# Board_7_Segment.net
KiCad netlist of a schematic drawn in EAGLE
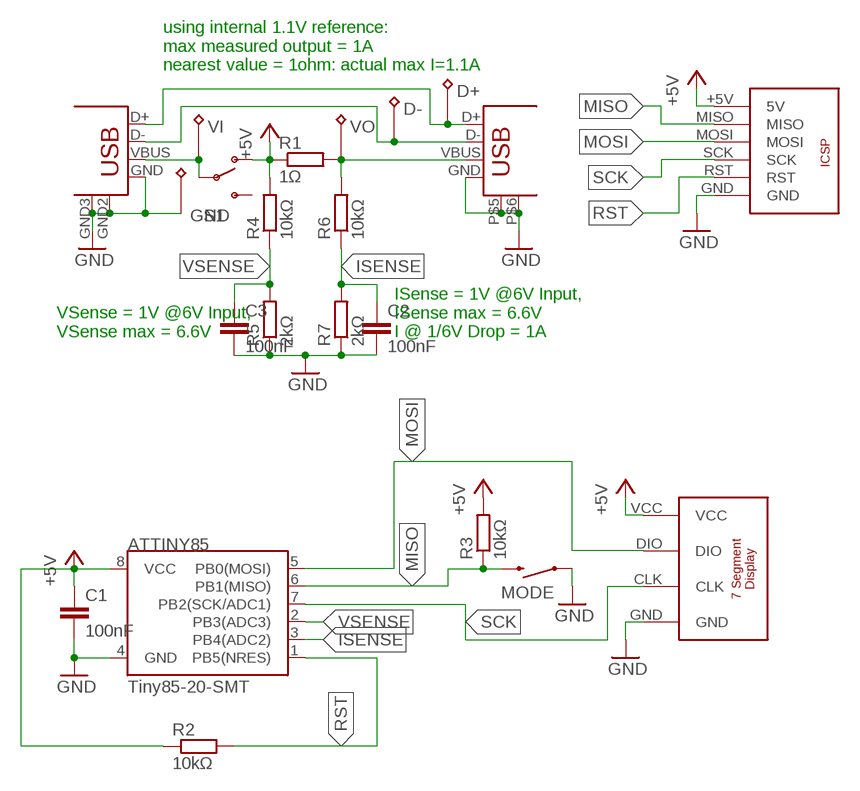
[diagram p0: schematic, sheet 1]

(export (version "E")
  (design (tool "Eeschema 10.0.6"))
  (components
    (comp (ref "ATTINY85")
      (value "Tiny85-20-SMT")
      (footprint "eagle-import:SO08-EIAJ")
      (libsource (lib "eagle-import") (part "ATTINY45TINY85-20-SMT"))
    )
    (comp (ref "C1")
      (value "100nF")
      (footprint "eagle-import:C0603")
      (libsource (lib "eagle-import") (part "C-EUC0603"))
    )
    (comp (ref "C2")
      (value "100nF")
      (footprint "eagle-import:C0603")
      (libsource (lib "eagle-import") (part "C-EUC0603"))
    )
    (comp (ref "C3")
      (value "100nF")
      (footprint "eagle-import:C0603")
      (libsource (lib "eagle-import") (part "C-EUC0603"))
    )
    (comp (ref "D+")
      (value "TESTPOINT0.8MM-DUAL-DRILL-WIRE-LOOP")
      (footprint "eagle-import:TP-0.8MM-DUAL")
      (libsource (lib "eagle-import") (part "TESTPOINT0.8MM-DUAL-DRILL-WIRE-LOOP"))
    )
    (comp (ref "D-")
      (value "TESTPOINT0.8MM-DUAL-DRILL-WIRE-LOOP")
      (footprint "eagle-import:TP-0.8MM-DUAL")
      (libsource (lib "eagle-import") (part "TESTPOINT0.8MM-DUAL-DRILL-WIRE-LOOP"))
    )
    (comp (ref "GND")
      (value "TESTPOINT0.8MM-DUAL-DRILL-WIRE-LOOP")
      (footprint "eagle-import:TP-0.8MM-DUAL")
      (libsource (lib "eagle-import") (part "TESTPOINT0.8MM-DUAL-DRILL-WIRE-LOOP"))
    )
    (comp (ref "INPUT")
      (value "USB+SHIELDTHROUGHHOLE-MALE")
      (footprint "eagle-import:USB-A-H")
      (libsource (lib "eagle-import") (part "USB+SHIELDTHROUGHHOLE-MALE"))
    )
    (comp (ref "MODE")
      (value "SWITCH-MOMENTARY-2SIDE_EZ")
      (footprint "eagle-import:TACTILE-PTH-SIDEEZ")
      (libsource (lib "eagle-import") (part "SWITCH-MOMENTARY-2SIDE_EZ"))
    )
    (comp (ref "OUTPUT")
      (value "USB+SHIELDTHROUGHOLE-FEMALE")
      (footprint "eagle-import:USB-A-S-SILK-THROUGHHOLE")
      (libsource (lib "eagle-import") (part "USB+SHIELDTHROUGHOLE-FEMALE"))
    )
    (comp (ref "R1")
      (value "1Ω")
      (footprint "eagle-import:R2512")
      (libsource (lib "eagle-import") (part "R-EU_R2512"))
    )
    (comp (ref "R2")
      (value "10kΩ")
      (footprint "eagle-import:R0603")
      (libsource (lib "eagle-import") (part "R-EU_R0603"))
    )
    (comp (ref "R3")
      (value "10kΩ")
      (footprint "eagle-import:R0603")
      (libsource (lib "eagle-import") (part "R-EU_R0603"))
    )
    (comp (ref "R4")
      (value "10kΩ")
      (footprint "eagle-import:R0603")
      (libsource (lib "eagle-import") (part "R-EU_R0603"))
    )
    (comp (ref "R5")
      (value "2kΩ")
      (footprint "eagle-import:R0603")
      (libsource (lib "eagle-import") (part "R-EU_R0603"))
    )
    (comp (ref "R6")
      (value "10kΩ")
      (footprint "eagle-import:R0603")
      (libsource (lib "eagle-import") (part "R-EU_R0603"))
    )
    (comp (ref "R7")
      (value "2kΩ")
      (footprint "eagle-import:R0603")
      (libsource (lib "eagle-import") (part "R-EU_R0603"))
    )
    (comp (ref "S1")
      (value "SWITCH-SPDT-SMD-A")
      (footprint "eagle-import:SWITCH-SPST-SMD-A")
      (libsource (lib "eagle-import") (part "SWITCH-SPDT-SMD-A"))
    )
    (comp (ref "U$1")
      (value "ICSPTHROUGHHOLE")
      (footprint "eagle-import:ICSP-THROUGHHOLE")
      (libsource (lib "eagle-import") (part "ICSPTHROUGHHOLE"))
    )
    (comp (ref "U$2")
      (value "7-SEGMENT-I2C")
      (footprint "eagle-import:7-SEGMENT-I2C")
      (libsource (lib "eagle-import") (part "7-SEGMENT-I2C"))
    )
    (comp (ref "VI")
      (value "TESTPOINT0.8MM-DUAL-DRILL-WIRE-LOOP")
      (footprint "eagle-import:TP-0.8MM-DUAL")
      (libsource (lib "eagle-import") (part "TESTPOINT0.8MM-DUAL-DRILL-WIRE-LOOP"))
    )
    (comp (ref "VO")
      (value "TESTPOINT0.8MM-DUAL-DRILL-WIRE-LOOP")
      (footprint "eagle-import:TP-0.8MM-DUAL")
      (libsource (lib "eagle-import") (part "TESTPOINT0.8MM-DUAL-DRILL-WIRE-LOOP"))
    )
  )
  (nets
    (net (code "1") (name "+5V") (class "Default")
      (node (ref "ATTINY85") (pin "8") (pinfunction "VCC_8") (pintype "bidirectional"))
      (node (ref "C1") (pin "1") (pinfunction "1_1") (pintype "passive"))
      (node (ref "R1") (pin "1") (pinfunction "1_1") (pintype "passive"))
      (node (ref "R2") (pin "1") (pinfunction "1_1") (pintype "passive"))
      (node (ref "R3") (pin "2") (pinfunction "2_2") (pintype "passive"))
      (node (ref "R4") (pin "2") (pinfunction "2_2") (pintype "passive"))
      (node (ref "S1") (pin "1") (pinfunction "O_1") (pintype "passive"))
      (node (ref "U$1") (pin "+5V") (pinfunction "5V_+5V") (pintype "bidirectional"))
      (node (ref "U$2") (pin "VCC") (pinfunction "VCC_VCC") (pintype "bidirectional"))
    )
    (net (code "2") (name "GND") (class "Default")
      (node (ref "ATTINY85") (pin "4") (pinfunction "GND_4") (pintype "bidirectional"))
      (node (ref "C1") (pin "2") (pinfunction "2_2") (pintype "passive"))
      (node (ref "C2") (pin "2") (pinfunction "2_2") (pintype "passive"))
      (node (ref "C3") (pin "2") (pinfunction "2_2") (pintype "passive"))
      (node (ref "GND") (pin "P$1") (pinfunction "TP_P$1") (pintype "bidirectional"))
      (node (ref "GND") (pin "P$2") (pinfunction "TP_P$2") (pintype "bidirectional"))
      (node (ref "INPUT") (pin "GND") (pinfunction "GND_GND") (pintype "bidirectional"))
      (node (ref "INPUT") (pin "GND2") (pinfunction "S1_GND2") (pintype "bidirectional"))
      (node (ref "INPUT") (pin "GND3") (pinfunction "S2_GND3") (pintype "bidirectional"))
      (node (ref "MODE") (pin "1") (pinfunction "1_1") (pintype "passive"))
      (node (ref "OUTPUT") (pin "GND") (pinfunction "GND_GND") (pintype "bidirectional"))
      (node (ref "OUTPUT") (pin "P$5") (pinfunction "S1_P$5") (pintype "bidirectional"))
      (node (ref "OUTPUT") (pin "P$6") (pinfunction "S2_P$6") (pintype "bidirectional"))
      (node (ref "R5") (pin "1") (pinfunction "1_1") (pintype "passive"))
      (node (ref "R7") (pin "1") (pinfunction "1_1") (pintype "passive"))
      (node (ref "U$1") (pin "GND") (pinfunction "GND_GND") (pintype "bidirectional"))
      (node (ref "U$2") (pin "GND") (pinfunction "GND_GND") (pintype "bidirectional"))
    )
    (net (code "3") (name "ISENSE") (class "Default")
      (node (ref "ATTINY85") (pin "3") (pinfunction "PB4(ADC2)_3") (pintype "bidirectional"))
      (node (ref "C2") (pin "1") (pinfunction "1_1") (pintype "passive"))
      (node (ref "R6") (pin "1") (pinfunction "1_1") (pintype "passive"))
      (node (ref "R7") (pin "2") (pinfunction "2_2") (pintype "passive"))
    )
    (net (code "4") (name "MISO") (class "Default")
      (node (ref "ATTINY85") (pin "6") (pinfunction "PB1(MISO)_6") (pintype "bidirectional"))
      (node (ref "MODE") (pin "2") (pinfunction "2_2") (pintype "passive"))
      (node (ref "R3") (pin "1") (pinfunction "1_1") (pintype "passive"))
      (node (ref "U$1") (pin "MISO") (pinfunction "MISO_MISO") (pintype "bidirectional"))
    )
    (net (code "5") (name "MOSI") (class "Default")
      (node (ref "ATTINY85") (pin "5") (pinfunction "PB0(MOSI)_5") (pintype "bidirectional"))
      (node (ref "U$1") (pin "MOSI") (pinfunction "MOSI_MOSI") (pintype "bidirectional"))
      (node (ref "U$2") (pin "DIO") (pinfunction "DIO_DIO") (pintype "bidirectional"))
    )
    (net (code "6") (name "Net-(D+-TP-PadP$1)") (class "Default")
      (node (ref "D+") (pin "P$1") (pinfunction "TP_P$1") (pintype "bidirectional"))
      (node (ref "D+") (pin "P$2") (pinfunction "TP_P$2") (pintype "bidirectional"))
      (node (ref "INPUT") (pin "D+") (pinfunction "D+_D+") (pintype "bidirectional"))
      (node (ref "OUTPUT") (pin "D+") (pinfunction "D+_D+") (pintype "bidirectional"))
    )
    (net (code "7") (name "Net-(D--TP-PadP$1)") (class "Default")
      (node (ref "D-") (pin "P$1") (pinfunction "TP_P$1") (pintype "bidirectional"))
      (node (ref "D-") (pin "P$2") (pinfunction "TP_P$2") (pintype "bidirectional"))
      (node (ref "INPUT") (pin "D-") (pinfunction "D-_D-") (pintype "bidirectional"))
      (node (ref "OUTPUT") (pin "D-") (pinfunction "D-_D-") (pintype "bidirectional"))
    )
    (net (code "8") (name "Net-(OUTPUT-PadVBUS)") (class "Default")
      (node (ref "OUTPUT") (pin "VBUS") (pinfunction "VBUS_VBUS") (pintype "bidirectional"))
      (node (ref "R1") (pin "2") (pinfunction "2_2") (pintype "passive"))
      (node (ref "R6") (pin "2") (pinfunction "2_2") (pintype "passive"))
      (node (ref "VO") (pin "P$1") (pinfunction "TP_P$1") (pintype "bidirectional"))
      (node (ref "VO") (pin "P$2") (pinfunction "TP_P$2") (pintype "bidirectional"))
    )
    (net (code "9") (name "Net-(S1-P)") (class "Default")
      (node (ref "INPUT") (pin "VBUS") (pinfunction "VBUS_VBUS") (pintype "bidirectional"))
      (node (ref "S1") (pin "2") (pinfunction "P_2") (pintype "passive"))
      (node (ref "VI") (pin "P$1") (pinfunction "TP_P$1") (pintype "bidirectional"))
      (node (ref "VI") (pin "P$2") (pinfunction "TP_P$2") (pintype "bidirectional"))
    )
    (net (code "10") (name "RST") (class "Default")
      (node (ref "ATTINY85") (pin "1") (pinfunction "PB5(NRES)_1") (pintype "bidirectional"))
      (node (ref "R2") (pin "2") (pinfunction "2_2") (pintype "passive"))
      (node (ref "U$1") (pin "RST") (pinfunction "RST_RST") (pintype "bidirectional"))
    )
    (net (code "11") (name "SCK") (class "Default")
      (node (ref "ATTINY85") (pin "7") (pinfunction "PB2(SCK/ADC1)_7") (pintype "bidirectional"))
      (node (ref "U$1") (pin "SCK") (pinfunction "SCK_SCK") (pintype "bidirectional"))
      (node (ref "U$2") (pin "CLK") (pinfunction "CLK_CLK") (pintype "bidirectional"))
    )
    (net (code "12") (name "VSENSE") (class "Default")
      (node (ref "ATTINY85") (pin "2") (pinfunction "PB3(ADC3)_2") (pintype "bidirectional"))
      (node (ref "C3") (pin "1") (pinfunction "1_1") (pintype "passive"))
      (node (ref "R4") (pin "1") (pinfunction "1_1") (pintype "passive"))
      (node (ref "R5") (pin "2") (pinfunction "2_2") (pintype "passive"))
    )
    (net (code "13") (name "unconnected-(S1-S-Pad3)") (class "Default")
      (node (ref "S1") (pin "3") (pinfunction "S_3") (pintype "passive"))
    )
  )
)
